# Precharge_schematic.net
KiCad netlist of a schematic drawn in Altium Designer
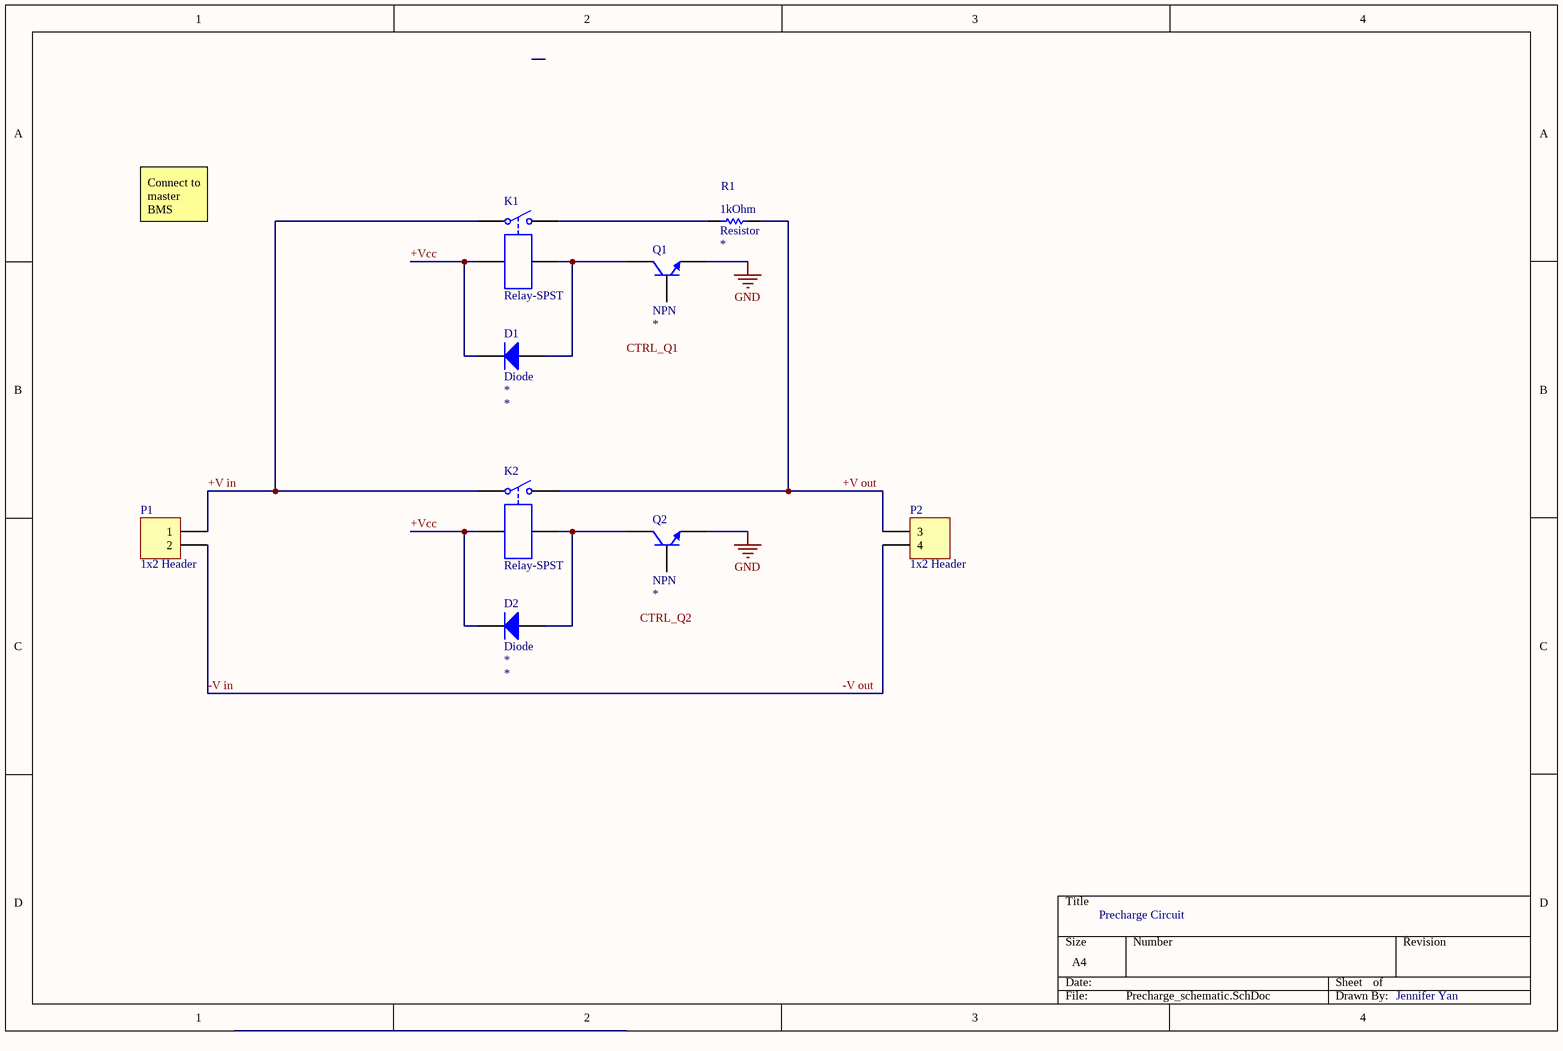
[diagram p0: Precharge_schematic.SchDoc]

(export (version "E")
  (design (tool "Eeschema 10.0.6"))
  (components
    (comp (ref "1kOhm")
      (value "Resistor")
      (footprint "0603 - Resistor")
      (fields (field (name "ALTIUM_VALUE") "*"))
      (libsource (lib "General") (part "Resistor"))
    )
    (comp (ref "D1")
      (value "Diode")
      (fields (field (name "ALTIUM_VALUE") "*") (field (name "MANUFACTURER PART NUMBER") "*"))
      (libsource (lib "General") (part "Diode"))
    )
    (comp (ref "D2")
      (value "Diode")
      (fields (field (name "ALTIUM_VALUE") "*") (field (name "MANUFACTURER PART NUMBER") "*"))
      (libsource (lib "General") (part "Diode"))
    )
    (comp (ref "K1")
      (value "Relay-SPST")
      (footprint "MODULE4")
      (description "Single-Pole Single-Throw Relay")
      (fields (field (name "PUBLISHER") "Altium Limited"))
      (libsource (lib "Miscellaneous Devices") (part "Relay-SPST"))
    )
    (comp (ref "K2")
      (value "Relay-SPST")
      (footprint "MODULE4")
      (description "Single-Pole Single-Throw Relay")
      (fields (field (name "PUBLISHER") "Altium Limited"))
      (libsource (lib "Miscellaneous Devices") (part "Relay-SPST"))
    )
    (comp (ref "P1")
      (value "1x2 Header")
      (description "1x2 Pin Header")
      (libsource (lib "") (part "1x2 Header_1"))
    )
    (comp (ref "P2")
      (value "1x2 Header")
      (description "1x2 Pin Header")
      (libsource (lib "GeneralConnectors") (part "1x2 Header"))
    )
    (comp (ref "Q1")
      (value "NPN")
      (description "NPN Bipolar Transistor")
      (fields (field (name "ALTIUM_VALUE") "*"))
      (libsource (lib "General") (part "NPN"))
    )
    (comp (ref "Q2")
      (value "NPN")
      (description "NPN Bipolar Transistor")
      (fields (field (name "ALTIUM_VALUE") "*"))
      (libsource (lib "General") (part "NPN"))
    )
  )
  (nets
    (net (code "1") (name "/+V in") (class "Default")
      (node (ref "K1") (pin "1") (pinfunction "1_1") (pintype "passive"))
      (node (ref "K2") (pin "1") (pinfunction "1_1") (pintype "passive"))
      (node (ref "P1") (pin "1") (pinfunction "1_1") (pintype "passive"))
    )
    (net (code "2") (name "/+V out") (class "Default")
      (node (ref "1kOhm") (pin "2") (pinfunction "2_2") (pintype "passive"))
      (node (ref "K2") (pin "2") (pinfunction "2_2") (pintype "passive"))
      (node (ref "P2") (pin "3") (pinfunction "3_3") (pintype "passive"))
    )
    (net (code "3") (name "/+Vcc") (class "Default")
      (node (ref "D1") (pin "2") (pinfunction "K_2") (pintype "passive"))
      (node (ref "D2") (pin "2") (pinfunction "K_2") (pintype "passive"))
      (node (ref "K1") (pin "3") (pinfunction "3_3") (pintype "passive"))
      (node (ref "K2") (pin "3") (pinfunction "3_3") (pintype "passive"))
    )
    (net (code "4") (name "/-V in") (class "Default")
      (node (ref "P1") (pin "2") (pinfunction "2_2") (pintype "passive"))
      (node (ref "P2") (pin "4") (pinfunction "4_4") (pintype "passive"))
    )
    (net (code "7") (name "GND") (class "Default")
      (node (ref "Q1") (pin "3") (pinfunction "E_3") (pintype "passive"))
      (node (ref "Q2") (pin "3") (pinfunction "E_3") (pintype "passive"))
    )
    (net (code "8") (name "Net-(1kOhm-Pad1)") (class "Default")
      (node (ref "1kOhm") (pin "1") (pinfunction "1_1") (pintype "passive"))
      (node (ref "K1") (pin "2") (pinfunction "2_2") (pintype "passive"))
    )
    (net (code "9") (name "Net-(D1-A)") (class "Default")
      (node (ref "D1") (pin "1") (pinfunction "A_1") (pintype "passive"))
      (node (ref "K1") (pin "4") (pinfunction "4_4") (pintype "passive"))
      (node (ref "Q1") (pin "1") (pinfunction "C_1") (pintype "passive"))
    )
    (net (code "10") (name "Net-(D2-A)") (class "Default")
      (node (ref "D2") (pin "1") (pinfunction "A_1") (pintype "passive"))
      (node (ref "K2") (pin "4") (pinfunction "4_4") (pintype "passive"))
      (node (ref "Q2") (pin "1") (pinfunction "C_1") (pintype "passive"))
    )
    (net (code "11") (name "unconnected-(Q1-B-Pad2)") (class "Default")
      (node (ref "Q1") (pin "2") (pinfunction "B_2") (pintype "passive"))
    )
    (net (code "12") (name "unconnected-(Q2-B-Pad2)") (class "Default")
      (node (ref "Q2") (pin "2") (pinfunction "B_2") (pintype "passive"))
    )
  )
)
